# BLE.net
KiCad netlist of a schematic drawn in Altium Designer
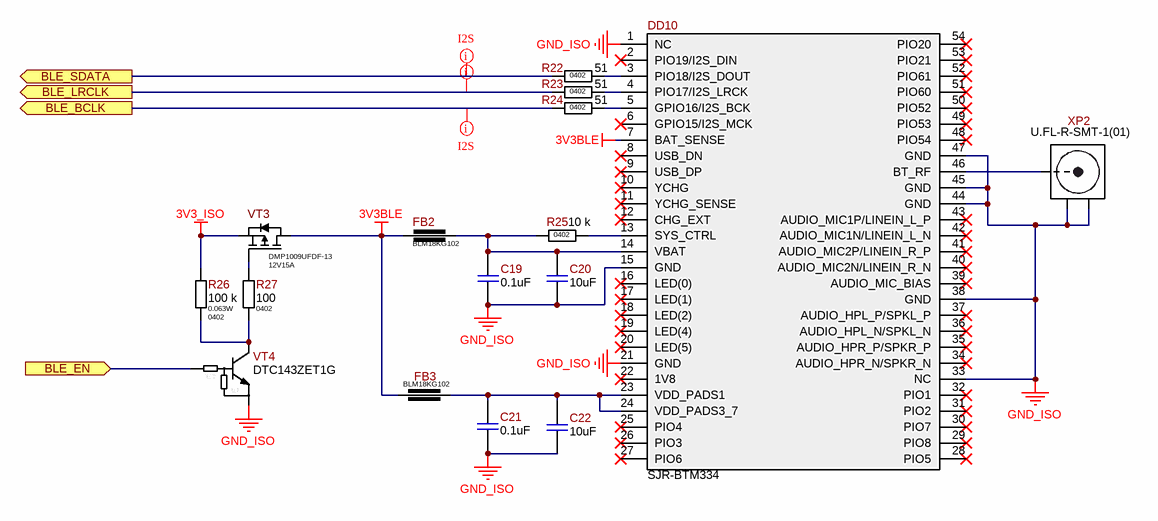
[diagram p0: BLE.SchDoc]

(export (version "E")
  (design (tool "Eeschema 10.0.6"))
  (components
    (comp (ref "C19")
      (value "0.1uF")
      (footprint "C0402(1005)")
      (description "CAP CER 0.1UF 25V X7R 0402")
      (fields (field (name "PART NUMBER") "0.1uF  25V C0402") (field (name "TOLERANCE") "±10%"))
      (libsource (lib "Database") (part "Capacitor_Ceramic"))
    )
    (comp (ref "C20")
      (value "10uF")
      (footprint "C0402(1005)")
      (description "CAP CER 10UF 6.3V X6S 0402")
      (fields (field (name "PART NUMBER") "10uF  6.3V C0402") (field (name "TOLERANCE") "±20%"))
      (libsource (lib "Database") (part "Capacitor_Ceramic"))
    )
    (comp (ref "C21")
      (value "0.1uF")
      (footprint "C0402(1005)")
      (description "CAP CER 0.1UF 25V X7R 0402")
      (fields (field (name "PART NUMBER") "0.1uF  25V C0402") (field (name "TOLERANCE") "±10%"))
      (libsource (lib "Database") (part "Capacitor_Ceramic"))
    )
    (comp (ref "C22")
      (value "10uF")
      (footprint "C0402(1005)")
      (description "CAP CER 10UF 6.3V X6S 0402")
      (fields (field (name "PART NUMBER") "10uF  6.3V C0402") (field (name "TOLERANCE") "±20%"))
      (libsource (lib "Database") (part "Capacitor_Ceramic"))
    )
    (comp (ref "DD10")
      (value "SJR-BTM334")
      (footprint "BTM334")
      (description "Bluetooth 5.1 audio module, QCC3034 chipset")
      (libsource (lib "Database") (part "BTM334"))
    )
    (comp (ref "FB2")
      (value "BLM18KG102")
      (footprint "BLM18(0603)")
      (description "FERRITE BEAD 1 KOHM 0603 1LN")
      (fields
        (field (name "TOLERANCE") "±25%")
        (field (name "MANUFACTURER") "Murata Electronics North America")
      )
      (libsource (lib "Database") (part "FB"))
    )
    (comp (ref "FB3")
      (value "BLM18KG102")
      (footprint "BLM18(0603)")
      (description "FERRITE BEAD 1 KOHM 0603 1LN")
      (fields
        (field (name "TOLERANCE") "±25%")
        (field (name "MANUFACTURER") "Murata Electronics North America")
      )
      (libsource (lib "Database") (part "FB"))
    )
    (comp (ref "R22")
      (value "51")
      (footprint "R0402")
      (description "RES SMD 51 OHM  ±1% 1/16W 0402")
      (fields
        (field (name "PACKAGE/CASE") "0402")
        (field (name "PART NUMBER") "51  R0402")
        (field (name "TOLERANCE") "±1%")
      )
      (libsource (lib "Database") (part "R0402"))
    )
    (comp (ref "R23")
      (value "51")
      (footprint "R0402")
      (description "RES SMD 51 OHM  ±1% 1/16W 0402")
      (fields
        (field (name "PACKAGE/CASE") "0402")
        (field (name "PART NUMBER") "51  R0402")
        (field (name "TOLERANCE") "±1%")
      )
      (libsource (lib "Database") (part "R0402"))
    )
    (comp (ref "R24")
      (value "51")
      (footprint "R0402")
      (description "RES SMD 51 OHM  ±1% 1/16W 0402")
      (fields
        (field (name "PACKAGE/CASE") "0402")
        (field (name "PART NUMBER") "51  R0402")
        (field (name "TOLERANCE") "±1%")
      )
      (libsource (lib "Database") (part "R0402"))
    )
    (comp (ref "R25")
      (value "10 k")
      (footprint "R0402")
      (description "RES SMD 10 k OHM  ±1% 1/16W 0402")
      (fields
        (field (name "PACKAGE/CASE") "0402")
        (field (name "PART NUMBER") "10 k  R0402")
        (field (name "TOLERANCE") "±1%")
      )
      (libsource (lib "Database") (part "R0402"))
    )
    (comp (ref "R26")
      (value "100 k")
      (footprint "R0402")
      (description "RES SMD 100 k OHM  ±1% 1/16W 0402")
      (fields
        (field (name "POWER RATING") "0.063W")
        (field (name "PACKAGE/CASE") "0402")
        (field (name "PART NUMBER") "100 k  R0402")
        (field (name "TOLERANCE") "±1%")
      )
      (libsource (lib "Database") (part "R0402"))
    )
    (comp (ref "R27")
      (value "100")
      (footprint "R0402")
      (description "RES SMD 100 OHM  ±1% 1/16W 0402")
      (fields
        (field (name "PACKAGE/CASE") "0402")
        (field (name "PART NUMBER") "100  R0402")
        (field (name "TOLERANCE") "±1%")
      )
      (libsource (lib "Database") (part "R0402"))
    )
    (comp (ref "VT3")
      (value "DMP1009UFDF-13")
      (footprint "U-DFN2020-6_SLDR")
      (description "P-Channel 12 V 15A (Ta) 2W (Ta) Surface Mount U-DFN2020-6 (Type F)")
      (fields (field (name "POWER RATING") "12V15A") (field (name "MANUFACTURER") "Diodes Incorporated"))
      (libsource (lib "Database") (part "DMP1009UFDF"))
    )
    (comp (ref "VT4")
      (value "DTC143ZET1G")
      (footprint "SOT-416")
      (description "TRANS PREBIAS NPN 50V 100MA SC75")
      (fields (field (name "MANUFACTURER") "onsemi"))
      (libsource (lib "Database") (part "Bipolar_NPN_Pre-Biased"))
    )
    (comp (ref "XP2")
      (value "U.FL-R-SMT-1(01)")
      (footprint "IPEX_ RECE.20279.001E.01")
      (description "CONN UMC RCPT STR 50 OHM SMD")
      (fields (field (name "MANUFACTURER") "HIROSE"))
      (libsource (lib "Database") (part "IPEX"))
    )
  )
  (nets
    (net (code "1") (name "/BLE_BCLK") (class "Default")
      (node (ref "R24") (pin "2") (pinfunction "2_2") (pintype "passive"))
    )
    (net (code "2") (name "/BLE_EN") (class "Default")
      (node (ref "VT4") (pin "1") (pinfunction "B_1") (pintype "passive"))
    )
    (net (code "3") (name "/BLE_LRCLK") (class "Default")
      (node (ref "R23") (pin "2") (pinfunction "2_2") (pintype "passive"))
    )
    (net (code "4") (name "/BLE_SDATA") (class "Default")
      (node (ref "R22") (pin "2") (pinfunction "2_2") (pintype "passive"))
    )
    (net (code "5") (name "3V3BLE") (class "Default")
      (node (ref "DD10") (pin "7") (pinfunction "BAT_SENSE_7") (pintype "passive"))
      (node (ref "FB2") (pin "1") (pintype "passive"))
      (node (ref "FB3") (pin "1") (pintype "passive"))
      (node (ref "VT3") (pin "D") (pinfunction "D_D") (pintype "passive"))
    )
    (net (code "6") (name "3V3_ISO") (class "Default")
      (node (ref "R26") (pin "1") (pinfunction "1_1") (pintype "passive"))
      (node (ref "VT3") (pin "S") (pinfunction "S_S") (pintype "passive"))
    )
    (net (code "7") (name "GND_ISO") (class "Default")
      (node (ref "C19") (pin "1") (pinfunction "1_1") (pintype "passive"))
      (node (ref "C20") (pin "1") (pinfunction "1_1") (pintype "passive"))
      (node (ref "C21") (pin "2") (pinfunction "2_2") (pintype "passive"))
      (node (ref "C22") (pin "1") (pinfunction "1_1") (pintype "passive"))
      (node (ref "DD10") (pin "1") (pinfunction "NC_1") (pintype "passive"))
      (node (ref "DD10") (pin "15") (pinfunction "GND_15") (pintype "passive"))
      (node (ref "DD10") (pin "21") (pinfunction "GND_21") (pintype "passive"))
      (node (ref "DD10") (pin "33") (pinfunction "NC_33") (pintype "passive"))
      (node (ref "DD10") (pin "38") (pinfunction "GND_38") (pintype "passive"))
      (node (ref "DD10") (pin "44") (pinfunction "GND_44") (pintype "passive"))
      (node (ref "DD10") (pin "45") (pinfunction "GND_45") (pintype "passive"))
      (node (ref "DD10") (pin "47") (pinfunction "GND_47") (pintype "passive"))
      (node (ref "VT4") (pin "2") (pinfunction "E_2") (pintype "passive"))
      (node (ref "XP2") (pin "2") (pinfunction "2_2") (pintype "passive"))
      (node (ref "XP2") (pin "3") (pinfunction "3_3") (pintype "passive"))
    )
    (net (code "8") (name "Net-(DD10-BT_RF)") (class "Default")
      (node (ref "DD10") (pin "46") (pinfunction "BT_RF_46") (pintype "passive"))
      (node (ref "XP2") (pin "1") (pinfunction "1_1") (pintype "passive"))
    )
    (net (code "9") (name "Net-(DD10-GPIO16{slash}I2S_BCK)") (class "Default")
      (node (ref "DD10") (pin "5") (pinfunction "GPIO16/I2S_BCK_5") (pintype "passive"))
      (node (ref "R24") (pin "1") (pinfunction "1_1") (pintype "passive"))
    )
    (net (code "10") (name "Net-(DD10-PIO17{slash}I2S_LRCK)") (class "Default")
      (node (ref "DD10") (pin "4") (pinfunction "PIO17/I2S_LRCK_4") (pintype "passive"))
      (node (ref "R23") (pin "1") (pinfunction "1_1") (pintype "passive"))
    )
    (net (code "11") (name "Net-(DD10-PIO18{slash}I2S_DOUT)") (class "Default")
      (node (ref "DD10") (pin "3") (pinfunction "PIO18/I2S_DOUT_3") (pintype "passive"))
      (node (ref "R22") (pin "1") (pinfunction "1_1") (pintype "passive"))
    )
    (net (code "12") (name "Net-(DD10-SYS_CTRL)") (class "Default")
      (node (ref "DD10") (pin "13") (pinfunction "SYS_CTRL_13") (pintype "passive"))
      (node (ref "R25") (pin "2") (pinfunction "2_2") (pintype "passive"))
    )
    (net (code "13") (name "Net-(DD10-VBAT)") (class "Default")
      (node (ref "C19") (pin "2") (pinfunction "2_2") (pintype "passive"))
      (node (ref "C20") (pin "2") (pinfunction "2_2") (pintype "passive"))
      (node (ref "DD10") (pin "14") (pinfunction "VBAT_14") (pintype "passive"))
      (node (ref "FB2") (pin "2") (pintype "passive"))
      (node (ref "R25") (pin "1") (pinfunction "1_1") (pintype "passive"))
    )
    (net (code "14") (name "Net-(DD10-VDD_PADS1)") (class "Default")
      (node (ref "C21") (pin "1") (pinfunction "1_1") (pintype "passive"))
      (node (ref "C22") (pin "2") (pinfunction "2_2") (pintype "passive"))
      (node (ref "DD10") (pin "23") (pinfunction "VDD_PADS1_23") (pintype "passive"))
      (node (ref "DD10") (pin "24") (pinfunction "VDD_PADS3_7_24") (pintype "passive"))
      (node (ref "FB3") (pin "2") (pintype "passive"))
    )
    (net (code "15") (name "Net-(R27-Pad2)") (class "Default")
      (node (ref "R27") (pin "2") (pinfunction "2_2") (pintype "passive"))
      (node (ref "VT3") (pin "G") (pinfunction "G_G") (pintype "passive"))
    )
    (net (code "16") (name "Net-(VT4-C)") (class "Default")
      (node (ref "R26") (pin "2") (pinfunction "2_2") (pintype "passive"))
      (node (ref "R27") (pin "1") (pinfunction "1_1") (pintype "passive"))
      (node (ref "VT4") (pin "3") (pinfunction "C_3") (pintype "passive"))
    )
    (net (code "17") (name "unconnected-(DD10-1V8-Pad22)") (class "Default")
      (node (ref "DD10") (pin "22") (pinfunction "1V8_22") (pintype "passive+no_connect"))
    )
    (net (code "18") (name "unconnected-(DD10-AUDIO_HPL_N{slash}SPKL_N-Pad36)") (class "Default")
      (node (ref "DD10") (pin "36") (pinfunction "AUDIO_HPL_N/SPKL_N_36") (pintype "passive+no_connect"))
    )
    (net (code "19") (name "unconnected-(DD10-AUDIO_HPL_P{slash}SPKL_P-Pad37)") (class "Default")
      (node (ref "DD10") (pin "37") (pinfunction "AUDIO_HPL_P/SPKL_P_37") (pintype "passive+no_connect"))
    )
    (net (code "20") (name "unconnected-(DD10-AUDIO_HPR_N{slash}SPKR_N-Pad34)") (class "Default")
      (node (ref "DD10") (pin "34") (pinfunction "AUDIO_HPR_N/SPKR_N_34") (pintype "passive+no_connect"))
    )
    (net (code "21") (name "unconnected-(DD10-AUDIO_HPR_P{slash}SPKR_P-Pad35)") (class "Default")
      (node (ref "DD10") (pin "35") (pinfunction "AUDIO_HPR_P/SPKR_P_35") (pintype "passive+no_connect"))
    )
    (net (code "22") (name "unconnected-(DD10-AUDIO_MIC1N{slash}LINEIN_L_N-Pad42)") (class "Default")
      (node (ref "DD10") (pin "42") (pinfunction "AUDIO_MIC1N/LINEIN_L_N_42") (pintype "passive+no_connect"))
    )
    (net (code "23") (name "unconnected-(DD10-AUDIO_MIC1P{slash}LINEIN_L_P-Pad43)") (class "Default")
      (node (ref "DD10") (pin "43") (pinfunction "AUDIO_MIC1P/LINEIN_L_P_43") (pintype "passive+no_connect"))
    )
    (net (code "24") (name "unconnected-(DD10-AUDIO_MIC2N{slash}LINEIN_R_N-Pad40)") (class "Default")
      (node (ref "DD10") (pin "40") (pinfunction "AUDIO_MIC2N/LINEIN_R_N_40") (pintype "passive+no_connect"))
    )
    (net (code "25") (name "unconnected-(DD10-AUDIO_MIC2P{slash}LINEIN_R_P-Pad41)") (class "Default")
      (node (ref "DD10") (pin "41") (pinfunction "AUDIO_MIC2P/LINEIN_R_P_41") (pintype "passive+no_connect"))
    )
    (net (code "26") (name "unconnected-(DD10-AUDIO_MIC_BIAS-Pad39)") (class "Default")
      (node (ref "DD10") (pin "39") (pinfunction "AUDIO_MIC_BIAS_39") (pintype "passive+no_connect"))
    )
    (net (code "27") (name "unconnected-(DD10-CHG_EXT-Pad12)") (class "Default")
      (node (ref "DD10") (pin "12") (pinfunction "CHG_EXT_12") (pintype "passive+no_connect"))
    )
    (net (code "28") (name "unconnected-(DD10-GPIO15{slash}I2S_MCK-Pad6)") (class "Default")
      (node (ref "DD10") (pin "6") (pinfunction "GPIO15/I2S_MCK_6") (pintype "passive+no_connect"))
    )
    (net (code "29") (name "unconnected-(DD10-LED(0)-Pad16)") (class "Default")
      (node (ref "DD10") (pin "16") (pinfunction "LED(0)_16") (pintype "passive+no_connect"))
    )
    (net (code "30") (name "unconnected-(DD10-LED(1)-Pad17)") (class "Default")
      (node (ref "DD10") (pin "17") (pinfunction "LED(1)_17") (pintype "passive+no_connect"))
    )
    (net (code "31") (name "unconnected-(DD10-LED(2)-Pad18)") (class "Default")
      (node (ref "DD10") (pin "18") (pinfunction "LED(2)_18") (pintype "passive+no_connect"))
    )
    (net (code "32") (name "unconnected-(DD10-LED(4)-Pad19)") (class "Default")
      (node (ref "DD10") (pin "19") (pinfunction "LED(4)_19") (pintype "passive+no_connect"))
    )
    (net (code "33") (name "unconnected-(DD10-LED(5)-Pad20)") (class "Default")
      (node (ref "DD10") (pin "20") (pinfunction "LED(5)_20") (pintype "passive+no_connect"))
    )
    (net (code "34") (name "unconnected-(DD10-PIO1-Pad32)") (class "Default")
      (node (ref "DD10") (pin "32") (pinfunction "PIO1_32") (pintype "passive+no_connect"))
    )
    (net (code "35") (name "unconnected-(DD10-PIO2-Pad31)") (class "Default")
      (node (ref "DD10") (pin "31") (pinfunction "PIO2_31") (pintype "passive+no_connect"))
    )
    (net (code "36") (name "unconnected-(DD10-PIO3-Pad26)") (class "Default")
      (node (ref "DD10") (pin "26") (pinfunction "PIO3_26") (pintype "passive+no_connect"))
    )
    (net (code "37") (name "unconnected-(DD10-PIO4-Pad25)") (class "Default")
      (node (ref "DD10") (pin "25") (pinfunction "PIO4_25") (pintype "passive+no_connect"))
    )
    (net (code "38") (name "unconnected-(DD10-PIO5-Pad28)") (class "Default")
      (node (ref "DD10") (pin "28") (pinfunction "PIO5_28") (pintype "passive+no_connect"))
    )
    (net (code "39") (name "unconnected-(DD10-PIO6-Pad27)") (class "Default")
      (node (ref "DD10") (pin "27") (pinfunction "PIO6_27") (pintype "passive+no_connect"))
    )
    (net (code "40") (name "unconnected-(DD10-PIO7-Pad30)") (class "Default")
      (node (ref "DD10") (pin "30") (pinfunction "PIO7_30") (pintype "passive+no_connect"))
    )
    (net (code "41") (name "unconnected-(DD10-PIO8-Pad29)") (class "Default")
      (node (ref "DD10") (pin "29") (pinfunction "PIO8_29") (pintype "passive+no_connect"))
    )
    (net (code "42") (name "unconnected-(DD10-PIO19{slash}I2S_DIN-Pad2)") (class "Default")
      (node (ref "DD10") (pin "2") (pinfunction "PIO19/I2S_DIN_2") (pintype "passive+no_connect"))
    )
    (net (code "43") (name "unconnected-(DD10-PIO20-Pad54)") (class "Default")
      (node (ref "DD10") (pin "54") (pinfunction "PIO20_54") (pintype "passive+no_connect"))
    )
    (net (code "44") (name "unconnected-(DD10-PIO21-Pad53)") (class "Default")
      (node (ref "DD10") (pin "53") (pinfunction "PIO21_53") (pintype "passive+no_connect"))
    )
    (net (code "45") (name "unconnected-(DD10-PIO52-Pad50)") (class "Default")
      (node (ref "DD10") (pin "50") (pinfunction "PIO52_50") (pintype "passive+no_connect"))
    )
    (net (code "46") (name "unconnected-(DD10-PIO53-Pad49)") (class "Default")
      (node (ref "DD10") (pin "49") (pinfunction "PIO53_49") (pintype "passive+no_connect"))
    )
    (net (code "47") (name "unconnected-(DD10-PIO54-Pad48)") (class "Default")
      (node (ref "DD10") (pin "48") (pinfunction "PIO54_48") (pintype "passive+no_connect"))
    )
    (net (code "48") (name "unconnected-(DD10-PIO60-Pad51)") (class "Default")
      (node (ref "DD10") (pin "51") (pinfunction "PIO60_51") (pintype "passive+no_connect"))
    )
    (net (code "49") (name "unconnected-(DD10-PIO61-Pad52)") (class "Default")
      (node (ref "DD10") (pin "52") (pinfunction "PIO61_52") (pintype "passive+no_connect"))
    )
    (net (code "50") (name "unconnected-(DD10-USB_DN-Pad8)") (class "Default")
      (node (ref "DD10") (pin "8") (pinfunction "USB_DN_8") (pintype "passive+no_connect"))
    )
    (net (code "51") (name "unconnected-(DD10-USB_DP-Pad9)") (class "Default")
      (node (ref "DD10") (pin "9") (pinfunction "USB_DP_9") (pintype "passive+no_connect"))
    )
    (net (code "52") (name "unconnected-(DD10-YCHG-Pad10)") (class "Default")
      (node (ref "DD10") (pin "10") (pinfunction "YCHG_10") (pintype "passive+no_connect"))
    )
    (net (code "53") (name "unconnected-(DD10-YCHG_SENSE-Pad11)") (class "Default")
      (node (ref "DD10") (pin "11") (pinfunction "YCHG_SENSE_11") (pintype "passive+no_connect"))
    )
  )
)
